# SparkFun_Refrigerator_Gas_Sensor_ZMOD445.net
KiCad netlist of a schematic drawn in EAGLE
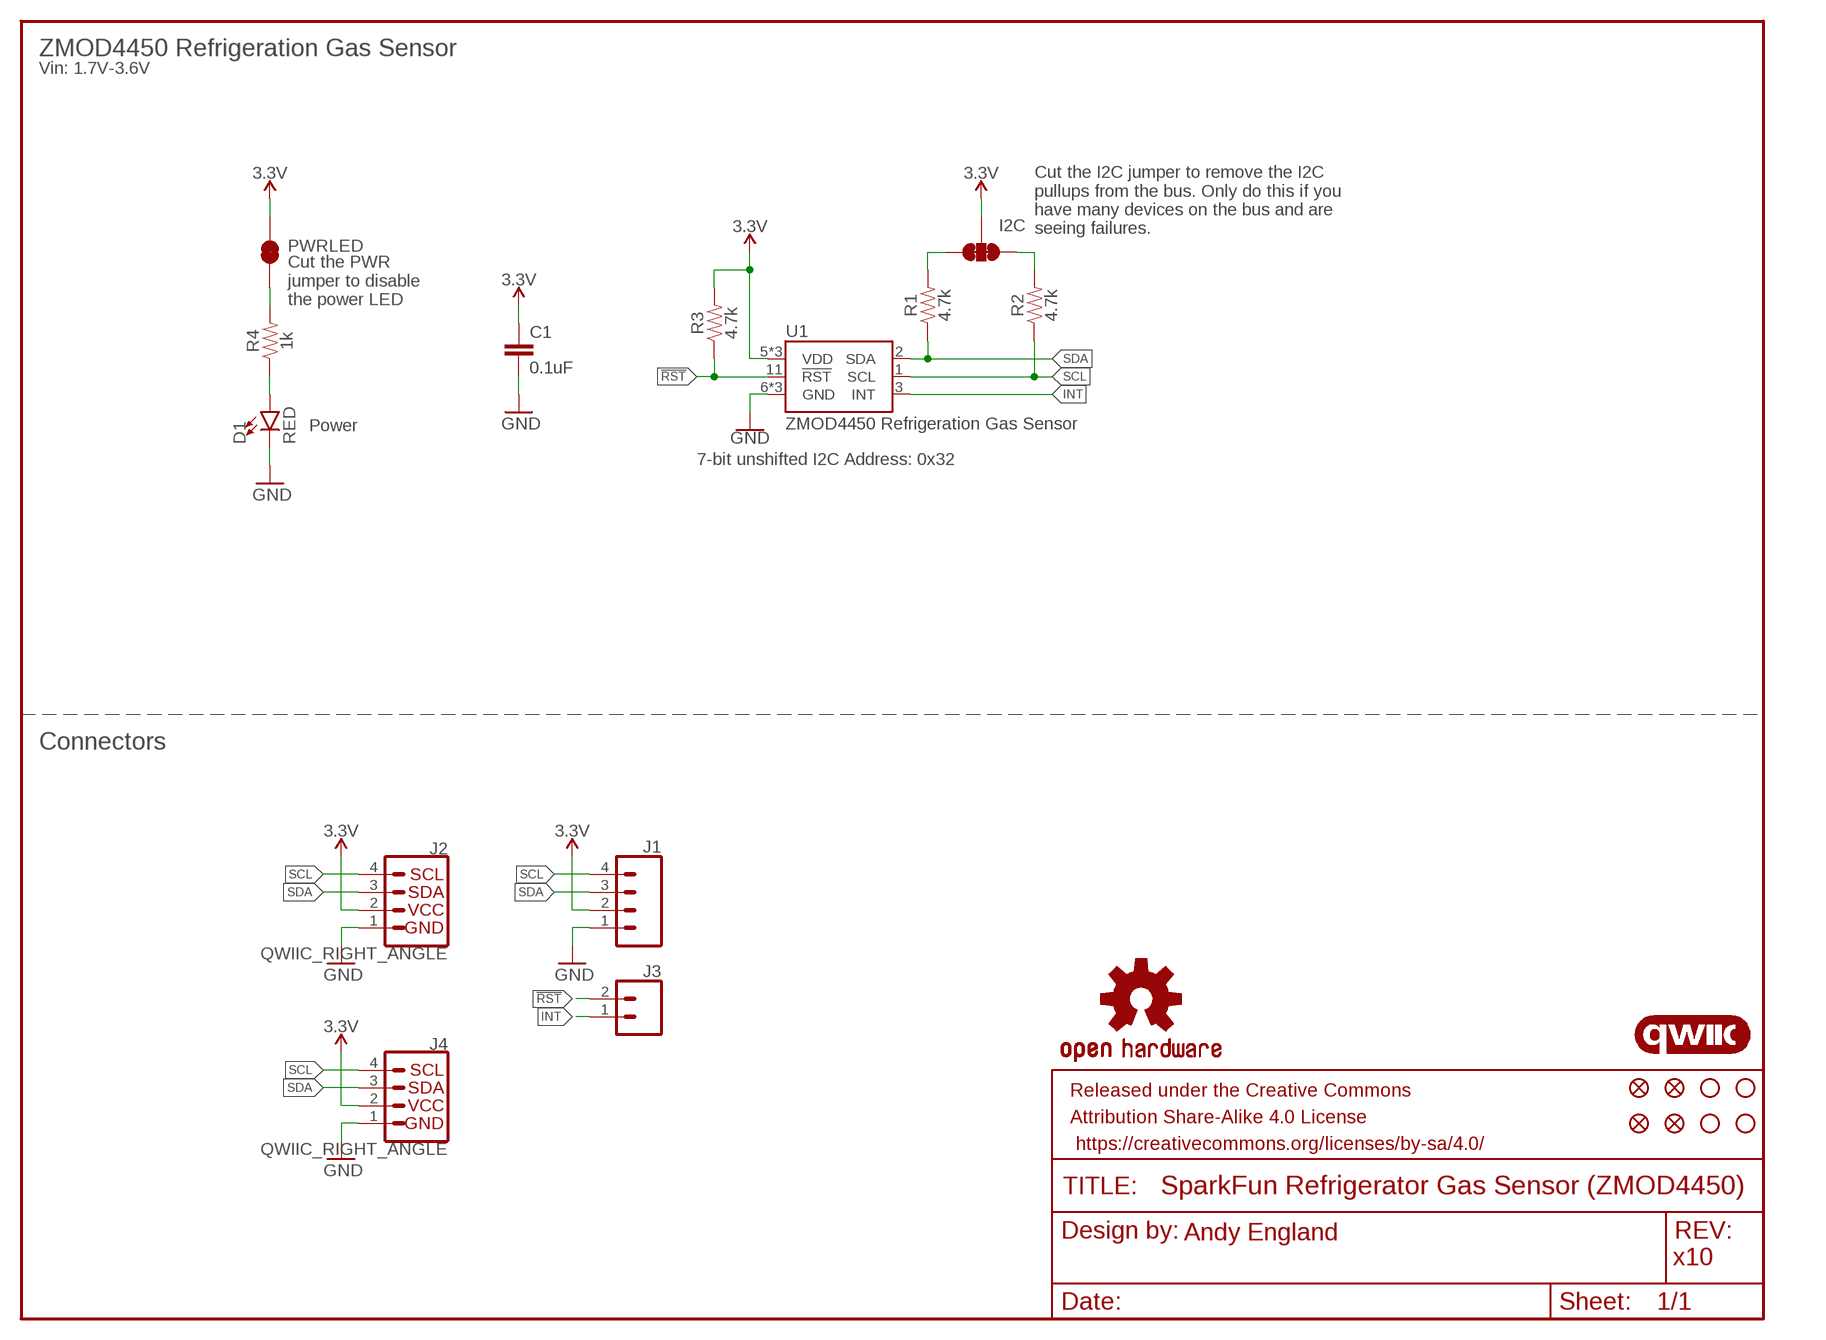
[diagram p0: schematic, sheet 1]

(export (version "E")
  (design (tool "Eeschema 10.0.6"))
  (components
    (comp (ref "C1")
      (value "0.1uF")
      (footprint "eagle-import:0603")
      (libsource (lib "eagle-import") (part "0.1UF-0603-25V-(+80/-20%)"))
    )
    (comp (ref "D1")
      (value "RED")
      (footprint "eagle-import:LED-0603")
      (libsource (lib "eagle-import") (part "LED-RED0603"))
    )
    (comp (ref "FD1")
      (value "FIDUCIALUFIDUCIAL")
      (footprint "eagle-import:FIDUCIAL-MICRO")
      (libsource (lib "eagle-import") (part "FIDUCIALUFIDUCIAL"))
    )
    (comp (ref "FD2")
      (value "FIDUCIALUFIDUCIAL")
      (footprint "eagle-import:FIDUCIAL-MICRO")
      (libsource (lib "eagle-import") (part "FIDUCIALUFIDUCIAL"))
    )
    (comp (ref "FD3")
      (value "FIDUCIALUFIDUCIAL")
      (footprint "eagle-import:FIDUCIAL-MICRO")
      (libsource (lib "eagle-import") (part "FIDUCIALUFIDUCIAL"))
    )
    (comp (ref "FD4")
      (value "FIDUCIALUFIDUCIAL")
      (footprint "eagle-import:FIDUCIAL-MICRO")
      (libsource (lib "eagle-import") (part "FIDUCIALUFIDUCIAL"))
    )
    (comp (ref "FRAME1")
      (value "FRAME-LETTER")
      (footprint "eagle-import:CREATIVE_COMMONS")
      (libsource (lib "eagle-import") (part "FRAME-LETTER"))
    )
    (comp (ref "H1")
      (value "STAND-OFF")
      (footprint "eagle-import:STAND-OFF")
      (libsource (lib "eagle-import") (part "STAND-OFF"))
    )
    (comp (ref "H2")
      (value "STAND-OFF")
      (footprint "eagle-import:STAND-OFF")
      (libsource (lib "eagle-import") (part "STAND-OFF"))
    )
    (comp (ref "H3")
      (value "STAND-OFF")
      (footprint "eagle-import:STAND-OFF")
      (libsource (lib "eagle-import") (part "STAND-OFF"))
    )
    (comp (ref "H4")
      (value "STAND-OFF")
      (footprint "eagle-import:STAND-OFF")
      (libsource (lib "eagle-import") (part "STAND-OFF"))
    )
    (comp (ref "I2C")
      (value "JUMPER-SMT_3_2-NC_TRACE_SILK")
      (footprint "eagle-import:SMT-JUMPER_3_2-NC_TRACE_SILK")
      (libsource (lib "eagle-import") (part "JUMPER-SMT_3_2-NC_TRACE_SILK"))
    )
    (comp (ref "J1")
      (value "CONN_041X04_NO_SILK")
      (footprint "eagle-import:1X04_NO_SILK")
      (libsource (lib "eagle-import") (part "CONN_041X04_NO_SILK"))
    )
    (comp (ref "J2")
      (value "QWIIC_RIGHT_ANGLE")
      (footprint "eagle-import:JST04_1MM_RA")
      (libsource (lib "eagle-import") (part "QWIIC_CONNECTORJS-1MM"))
    )
    (comp (ref "J3")
      (value "CONN_021X02_NO_SILK")
      (footprint "eagle-import:1X02_NO_SILK")
      (libsource (lib "eagle-import") (part "CONN_021X02_NO_SILK"))
    )
    (comp (ref "J4")
      (value "QWIIC_RIGHT_ANGLE")
      (footprint "eagle-import:JST04_1MM_RA")
      (libsource (lib "eagle-import") (part "QWIIC_CONNECTORJS-1MM"))
    )
    (comp (ref "LOGO1")
      (value "OSHW-LOGOS")
      (footprint "eagle-import:OSHW-LOGO-S")
      (libsource (lib "eagle-import") (part "OSHW-LOGOS"))
    )
    (comp (ref "LOGO2")
      (value "QWIIC_LOGO_5MM")
      (footprint "eagle-import:QWIIC_5MM")
      (libsource (lib "eagle-import") (part "QWIIC_LOGO_5MM"))
    )
    (comp (ref "PWRLED")
      (value "JUMPER-SMT_2_NC_TRACE_SILK")
      (footprint "eagle-import:SMT-JUMPER_2_NC_TRACE_SILK")
      (libsource (lib "eagle-import") (part "JUMPER-SMT_2_NC_TRACE_SILK"))
    )
    (comp (ref "R1")
      (value "4.7k")
      (footprint "eagle-import:0603")
      (libsource (lib "eagle-import") (part "4.7KOHM-0603-1/10W-1%"))
    )
    (comp (ref "R2")
      (value "4.7k")
      (footprint "eagle-import:0603")
      (libsource (lib "eagle-import") (part "4.7KOHM-0603-1/10W-1%"))
    )
    (comp (ref "R3")
      (value "4.7k")
      (footprint "eagle-import:0603")
      (libsource (lib "eagle-import") (part "4.7KOHM-0603-1/10W-1%"))
    )
    (comp (ref "R4")
      (value "1k")
      (footprint "eagle-import:0603")
      (libsource (lib "eagle-import") (part "1KOHM-0603-1/10W-1%"))
    )
    (comp (ref "U1")
      (value "ZMOD4450 Refrigeration Gas Sensor")
      (footprint "eagle-import:LGA-12-3X3")
      (libsource (lib "eagle-import") (part "ZMOD4450"))
    )
  )
  (nets
    (net (code "1") (name "/~{RST}") (class "Default")
      (node (ref "J3") (pin "2") (pinfunction "2_2") (pintype "passive"))
      (node (ref "R3") (pin "1") (pinfunction "1_1") (pintype "passive"))
      (node (ref "U1") (pin "11") (pinfunction "~{RST}_11") (pintype "bidirectional"))
    )
    (net (code "2") (name "3.3V") (class "Default")
      (node (ref "C1") (pin "1") (pinfunction "1_1") (pintype "passive"))
      (node (ref "I2C") (pin "2") (pinfunction "2_2") (pintype "passive"))
      (node (ref "J1") (pin "2") (pinfunction "2_2") (pintype "passive"))
      (node (ref "J2") (pin "2") (pinfunction "2_2") (pintype "power_in"))
      (node (ref "J4") (pin "2") (pinfunction "2_2") (pintype "power_in"))
      (node (ref "PWRLED") (pin "2") (pinfunction "2_2") (pintype "passive"))
      (node (ref "R3") (pin "2") (pinfunction "2_2") (pintype "passive"))
      (node (ref "U1") (pin "10") (pinfunction "VDD_10") (pintype "bidirectional"))
      (node (ref "U1") (pin "12") (pinfunction "VDD_12") (pintype "bidirectional"))
      (node (ref "U1") (pin "5") (pinfunction "VDD_5") (pintype "bidirectional"))
    )
    (net (code "3") (name "GND") (class "Default")
      (node (ref "C1") (pin "2") (pinfunction "2_2") (pintype "passive"))
      (node (ref "D1") (pin "C") (pinfunction "C_C") (pintype "passive"))
      (node (ref "J1") (pin "1") (pinfunction "1_1") (pintype "passive"))
      (node (ref "J2") (pin "1") (pinfunction "1_1") (pintype "power_in"))
      (node (ref "J4") (pin "1") (pinfunction "1_1") (pintype "power_in"))
      (node (ref "U1") (pin "6") (pinfunction "GND_6") (pintype "bidirectional"))
      (node (ref "U1") (pin "7") (pinfunction "GND_7") (pintype "bidirectional"))
      (node (ref "U1") (pin "9") (pinfunction "GND_9") (pintype "bidirectional"))
    )
    (net (code "4") (name "INT") (class "Default")
      (node (ref "J3") (pin "1") (pinfunction "1_1") (pintype "passive"))
      (node (ref "U1") (pin "3") (pinfunction "INT_3") (pintype "bidirectional"))
    )
    (net (code "5") (name "Net-(D1-PadA)") (class "Default")
      (node (ref "D1") (pin "A") (pinfunction "A_A") (pintype "passive"))
      (node (ref "R4") (pin "1") (pinfunction "1_1") (pintype "passive"))
    )
    (net (code "6") (name "Net-(I2C-Pad1)") (class "Default")
      (node (ref "I2C") (pin "1") (pinfunction "1_1") (pintype "passive"))
      (node (ref "R2") (pin "2") (pinfunction "2_2") (pintype "passive"))
    )
    (net (code "7") (name "Net-(I2C-Pad3)") (class "Default")
      (node (ref "I2C") (pin "3") (pinfunction "3_3") (pintype "passive"))
      (node (ref "R1") (pin "2") (pinfunction "2_2") (pintype "passive"))
    )
    (net (code "8") (name "Net-(PWRLED-Pad1)") (class "Default")
      (node (ref "PWRLED") (pin "1") (pinfunction "1_1") (pintype "passive"))
      (node (ref "R4") (pin "2") (pinfunction "2_2") (pintype "passive"))
    )
    (net (code "9") (name "SCL") (class "Default")
      (node (ref "J1") (pin "4") (pinfunction "4_4") (pintype "passive"))
      (node (ref "J2") (pin "4") (pinfunction "4_4") (pintype "passive"))
      (node (ref "J4") (pin "4") (pinfunction "4_4") (pintype "passive"))
      (node (ref "R2") (pin "1") (pinfunction "1_1") (pintype "passive"))
      (node (ref "U1") (pin "1") (pinfunction "SCL_1") (pintype "bidirectional"))
    )
    (net (code "10") (name "SDA") (class "Default")
      (node (ref "J1") (pin "3") (pinfunction "3_3") (pintype "passive"))
      (node (ref "J2") (pin "3") (pinfunction "3_3") (pintype "passive"))
      (node (ref "J4") (pin "3") (pinfunction "3_3") (pintype "passive"))
      (node (ref "R1") (pin "1") (pinfunction "1_1") (pintype "passive"))
      (node (ref "U1") (pin "2") (pinfunction "SDA_2") (pintype "bidirectional"))
    )
  )
)
